# POWER.net
KiCad netlist of a schematic drawn in Altium Designer
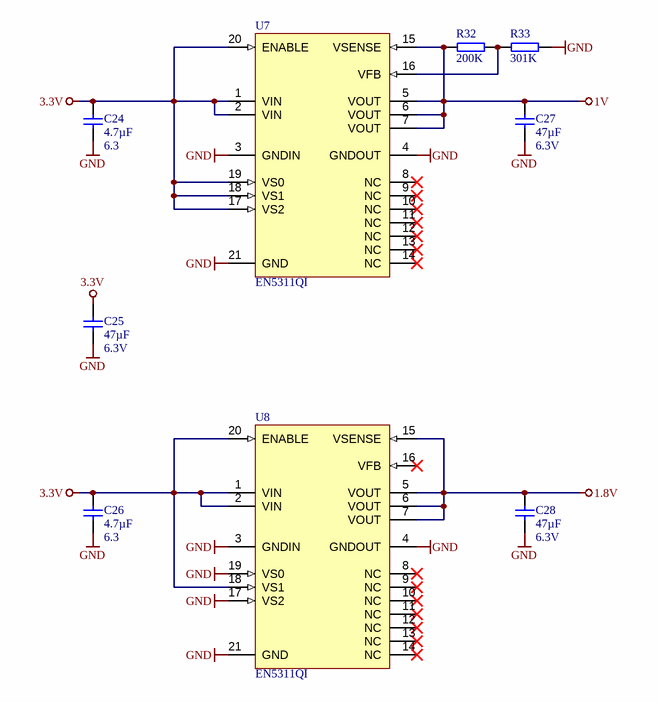
[diagram p0: POWER.SchDoc]

(export (version "E")
  (design (tool "Eeschema 10.0.6"))
  (components
    (comp (ref "C24")
      (value "4.7µF")
      (footprint "CAPC1005X60N")
      (description "KON 4.7µF 6.3V X5R SMD")
      (fields (field (name "VOLTAGE") "6.3"))
      (libsource (lib "TE") (part "CAP-NP"))
    )
    (comp (ref "C25")
      (value "47µF")
      (footprint "CAPC3216X180N")
      (description "KON 47µF 6.3V  X5R SMD 20%")
      (fields (field (name "VOLTAGE") "6.3V") (field (name "TOLERANCE") "20%"))
      (libsource (lib "TE") (part "CAP-NP"))
    )
    (comp (ref "C26")
      (value "4.7µF")
      (footprint "CAPC1005X60N")
      (description "KON 4.7µF 6.3V X5R SMD")
      (fields (field (name "VOLTAGE") "6.3"))
      (libsource (lib "TE") (part "CAP-NP"))
    )
    (comp (ref "C27")
      (value "47µF")
      (footprint "CAPC3216X180N")
      (description "KON 47µF 6.3V  X5R SMD 20%")
      (fields (field (name "VOLTAGE") "6.3V") (field (name "TOLERANCE") "20%"))
      (libsource (lib "TE") (part "CAP-NP"))
    )
    (comp (ref "C28")
      (value "47µF")
      (footprint "CAPC3216X180N")
      (description "KON 47µF 6.3V  X5R SMD 20%")
      (fields (field (name "VOLTAGE") "6.3V") (field (name "TOLERANCE") "20%"))
      (libsource (lib "TE") (part "CAP-NP"))
    )
    (comp (ref "R32")
      (value "200K")
      (footprint "RESC1005X40N")
      (description "WID SMD 200K 1% 0,063W")
      (libsource (lib "TE") (part "RES"))
    )
    (comp (ref "R33")
      (value "301K")
      (footprint "RESC1005X40N")
      (description "WID SMD 301K 1% 0,063W")
      (fields (field (name "TOLERANCE") "1%"))
      (libsource (lib "TE") (part "RES"))
    )
    (comp (ref "U7") (value "EN5311QI") (footprint "EN5311QI") (libsource (lib "TE") (part "EN5311QI")))
    (comp (ref "U8") (value "EN5311QI") (footprint "EN5311QI") (libsource (lib "TE") (part "EN5311QI")))
  )
  (nets
    (net (code "1") (name "1.8V") (class "Default")
      (node (ref "C28") (pin "1") (pinfunction "1_1") (pintype "passive"))
      (node (ref "U8") (pin "15") (pinfunction "VSENSE_15") (pintype "input"))
      (node (ref "U8") (pin "5") (pinfunction "VOUT_5") (pintype "power_in"))
      (node (ref "U8") (pin "6") (pinfunction "VOUT_6") (pintype "power_in"))
      (node (ref "U8") (pin "7") (pinfunction "VOUT_7") (pintype "power_in"))
    )
    (net (code "2") (name "1V") (class "Default")
      (node (ref "C27") (pin "1") (pinfunction "1_1") (pintype "passive"))
      (node (ref "R32") (pin "1") (pinfunction "1_1") (pintype "passive"))
      (node (ref "U7") (pin "15") (pinfunction "VSENSE_15") (pintype "input"))
      (node (ref "U7") (pin "5") (pinfunction "VOUT_5") (pintype "power_in"))
      (node (ref "U7") (pin "6") (pinfunction "VOUT_6") (pintype "power_in"))
      (node (ref "U7") (pin "7") (pinfunction "VOUT_7") (pintype "power_in"))
    )
    (net (code "3") (name "3.3V") (class "Default")
      (node (ref "C24") (pin "1") (pinfunction "1_1") (pintype "passive"))
      (node (ref "C25") (pin "1") (pinfunction "1_1") (pintype "passive"))
      (node (ref "C26") (pin "1") (pinfunction "1_1") (pintype "passive"))
      (node (ref "U7") (pin "1") (pinfunction "VIN_1") (pintype "power_in"))
      (node (ref "U7") (pin "17") (pinfunction "VS2_17") (pintype "input"))
      (node (ref "U7") (pin "18") (pinfunction "VS1_18") (pintype "input"))
      (node (ref "U7") (pin "19") (pinfunction "VS0_19") (pintype "input"))
      (node (ref "U7") (pin "2") (pinfunction "VIN_2") (pintype "power_in"))
      (node (ref "U7") (pin "20") (pinfunction "ENABLE_20") (pintype "input"))
      (node (ref "U8") (pin "1") (pinfunction "VIN_1") (pintype "power_in"))
      (node (ref "U8") (pin "18") (pinfunction "VS1_18") (pintype "input"))
      (node (ref "U8") (pin "2") (pinfunction "VIN_2") (pintype "power_in"))
      (node (ref "U8") (pin "20") (pinfunction "ENABLE_20") (pintype "input"))
    )
    (net (code "4") (name "GND") (class "Default")
      (node (ref "C24") (pin "2") (pinfunction "2_2") (pintype "passive"))
      (node (ref "C25") (pin "2") (pinfunction "2_2") (pintype "passive"))
      (node (ref "C26") (pin "2") (pinfunction "2_2") (pintype "passive"))
      (node (ref "C27") (pin "2") (pinfunction "2_2") (pintype "passive"))
      (node (ref "C28") (pin "2") (pinfunction "2_2") (pintype "passive"))
      (node (ref "R33") (pin "2") (pinfunction "2_2") (pintype "passive"))
      (node (ref "U7") (pin "21") (pinfunction "GND_21") (pintype "power_in"))
      (node (ref "U7") (pin "3") (pinfunction "GNDIN_3") (pintype "power_in"))
      (node (ref "U7") (pin "4") (pinfunction "GNDOUT_4") (pintype "power_in"))
      (node (ref "U8") (pin "17") (pinfunction "VS2_17") (pintype "input"))
      (node (ref "U8") (pin "19") (pinfunction "VS0_19") (pintype "input"))
      (node (ref "U8") (pin "21") (pinfunction "GND_21") (pintype "power_in"))
      (node (ref "U8") (pin "3") (pinfunction "GNDIN_3") (pintype "power_in"))
      (node (ref "U8") (pin "4") (pinfunction "GNDOUT_4") (pintype "power_in"))
    )
    (net (code "5") (name "Net-(U7-VFB)") (class "Default")
      (node (ref "R32") (pin "2") (pinfunction "2_2") (pintype "passive"))
      (node (ref "R33") (pin "1") (pinfunction "1_1") (pintype "passive"))
      (node (ref "U7") (pin "16") (pinfunction "VFB_16") (pintype "input"))
    )
    (net (code "6") (name "unconnected-(U7-NC-Pad8)") (class "Default")
      (node (ref "U7") (pin "8") (pinfunction "NC_8") (pintype "passive+no_connect"))
    )
    (net (code "7") (name "unconnected-(U7-NC-Pad9)") (class "Default")
      (node (ref "U7") (pin "9") (pinfunction "NC_9") (pintype "passive+no_connect"))
    )
    (net (code "8") (name "unconnected-(U7-NC-Pad10)") (class "Default")
      (node (ref "U7") (pin "10") (pinfunction "NC_10") (pintype "passive+no_connect"))
    )
    (net (code "9") (name "unconnected-(U7-NC-Pad11)") (class "Default")
      (node (ref "U7") (pin "11") (pinfunction "NC_11") (pintype "passive+no_connect"))
    )
    (net (code "10") (name "unconnected-(U7-NC-Pad12)") (class "Default")
      (node (ref "U7") (pin "12") (pinfunction "NC_12") (pintype "passive+no_connect"))
    )
    (net (code "11") (name "unconnected-(U7-NC-Pad13)") (class "Default")
      (node (ref "U7") (pin "13") (pinfunction "NC_13") (pintype "passive+no_connect"))
    )
    (net (code "12") (name "unconnected-(U7-NC-Pad14)") (class "Default")
      (node (ref "U7") (pin "14") (pinfunction "NC_14") (pintype "passive+no_connect"))
    )
    (net (code "13") (name "unconnected-(U8-NC-Pad8)") (class "Default")
      (node (ref "U8") (pin "8") (pinfunction "NC_8") (pintype "passive+no_connect"))
    )
    (net (code "14") (name "unconnected-(U8-NC-Pad9)") (class "Default")
      (node (ref "U8") (pin "9") (pinfunction "NC_9") (pintype "passive+no_connect"))
    )
    (net (code "15") (name "unconnected-(U8-NC-Pad10)") (class "Default")
      (node (ref "U8") (pin "10") (pinfunction "NC_10") (pintype "passive+no_connect"))
    )
    (net (code "16") (name "unconnected-(U8-NC-Pad11)") (class "Default")
      (node (ref "U8") (pin "11") (pinfunction "NC_11") (pintype "passive+no_connect"))
    )
    (net (code "17") (name "unconnected-(U8-NC-Pad12)") (class "Default")
      (node (ref "U8") (pin "12") (pinfunction "NC_12") (pintype "passive+no_connect"))
    )
    (net (code "18") (name "unconnected-(U8-NC-Pad13)") (class "Default")
      (node (ref "U8") (pin "13") (pinfunction "NC_13") (pintype "passive+no_connect"))
    )
    (net (code "19") (name "unconnected-(U8-NC-Pad14)") (class "Default")
      (node (ref "U8") (pin "14") (pinfunction "NC_14") (pintype "passive+no_connect"))
    )
    (net (code "20") (name "unconnected-(U8-VFB-Pad16)") (class "Default")
      (node (ref "U8") (pin "16") (pinfunction "VFB_16") (pintype "input+no_connect"))
    )
  )
)
